# xes_cabling.net
KiCad netlist of a schematic drawn in EAGLE
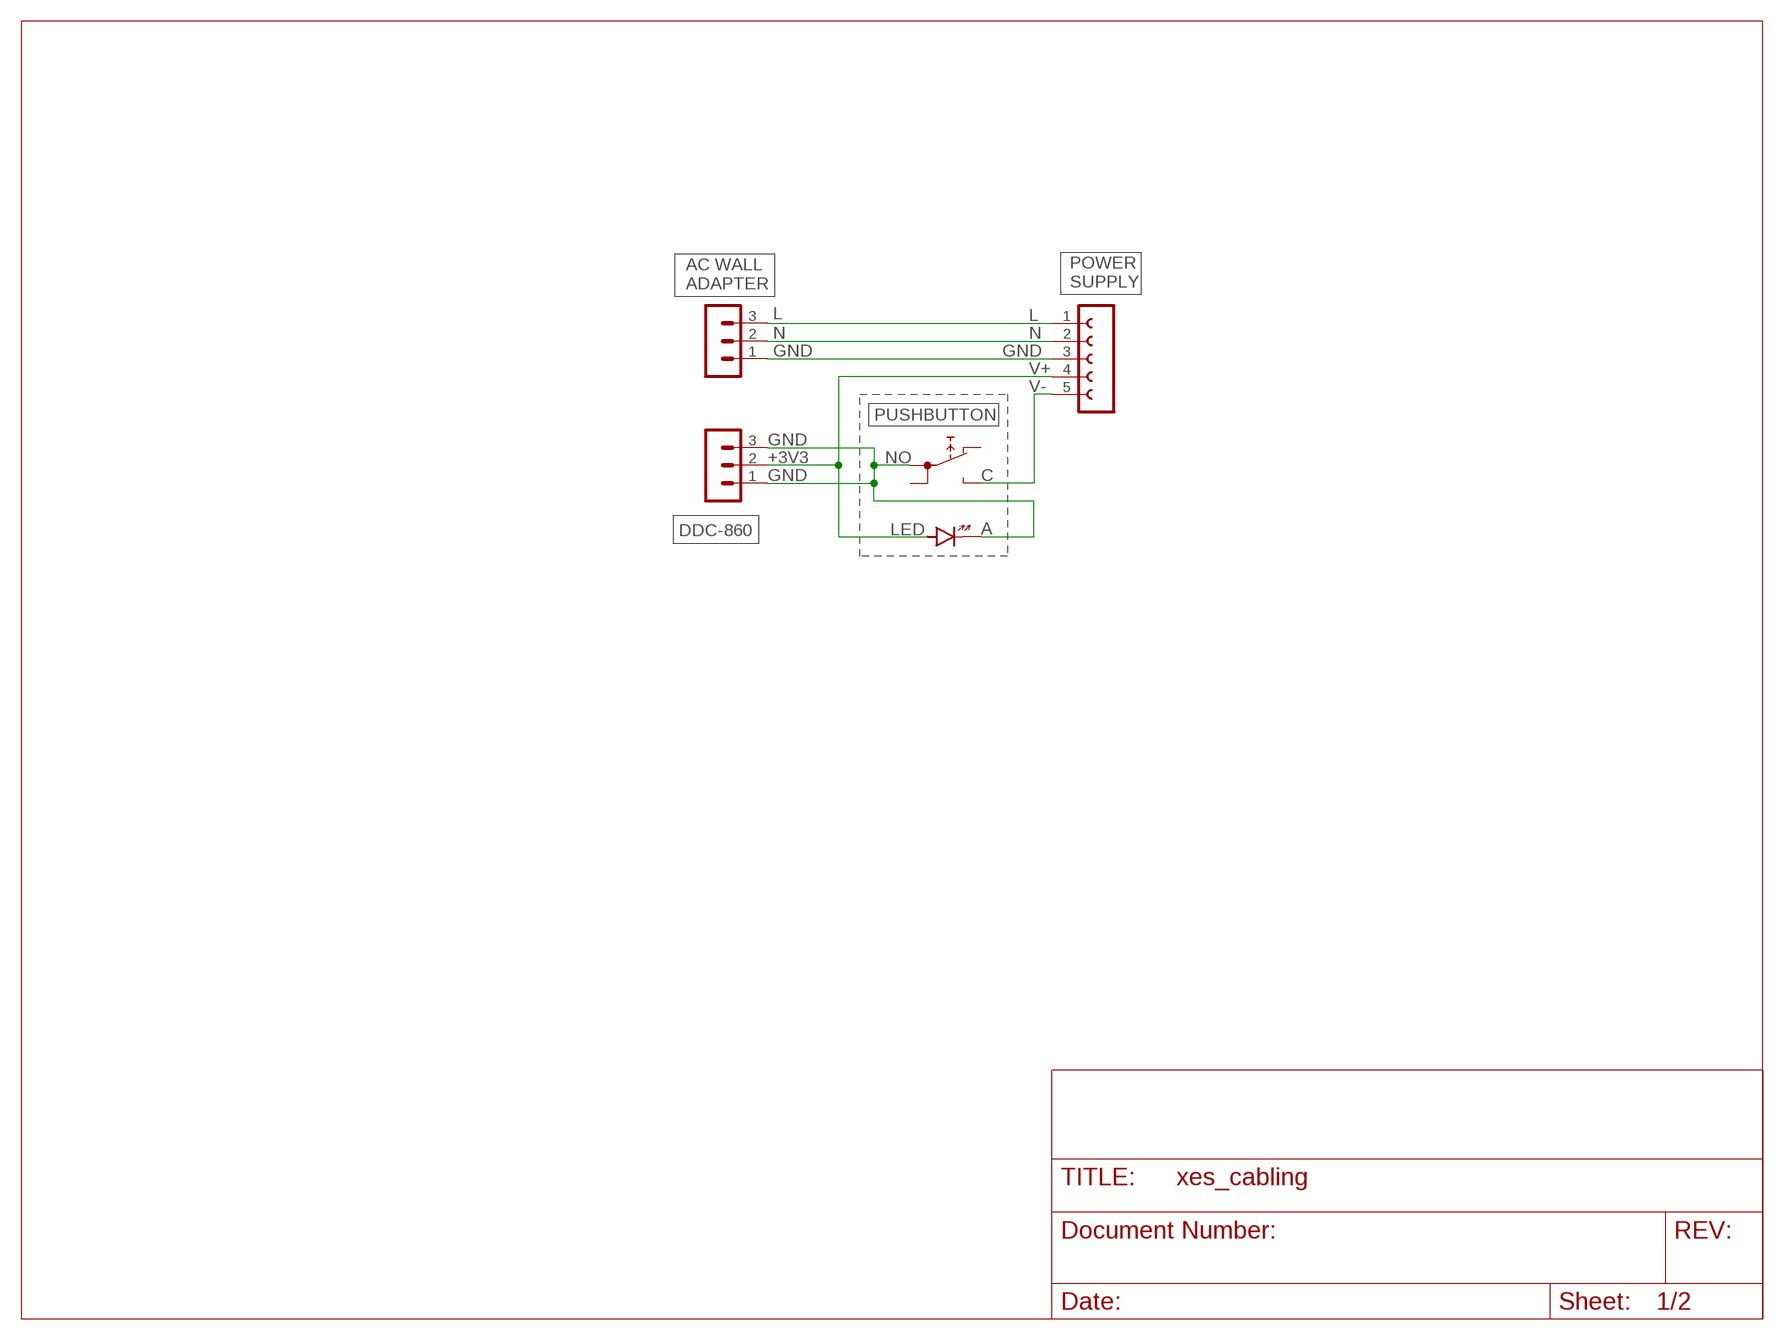
[diagram p0: schematic, sheet 1]
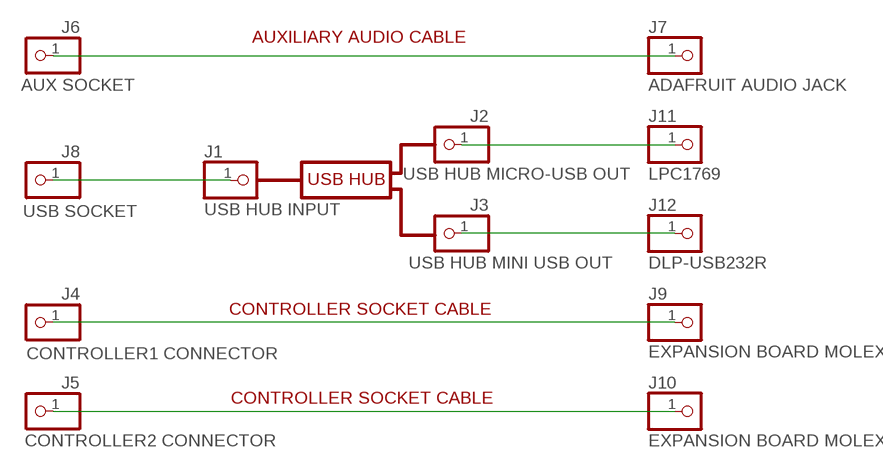
[diagram p1: schematic, sheet 2]

(export (version "E")
  (design (tool "Eeschema 10.0.6"))
  (components
    (comp (ref "LS25-3.3")
      (value "PSU")
      (footprint "eagle-import:FE05-1")
      (libsource (lib "eagle-import") (part "FE05-1"))
    )
    (comp (ref "S1")
      (value "PUSHBUTTON")
      (footprint "eagle-import:5501-1LED")
      (libsource (lib "eagle-import") (part "55?-1LED01"))
    )
    (comp (ref "SV1")
      (value "MA03-1")
      (footprint "eagle-import:MA03-1")
      (libsource (lib "eagle-import") (part "MA03-1"))
    )
    (comp (ref "SV2")
      (value "MA03-1")
      (footprint "eagle-import:MA03-1")
      (libsource (lib "eagle-import") (part "MA03-1"))
    )
    (comp (ref "J1")
      (value "USB HUB INPUT")
      (footprint "eagle-import:1X01")
      (libsource (lib "eagle-import") (part "PINHD-1X1"))
    )
    (comp (ref "J2")
      (value "USB HUB MICRO-USB OUT")
      (footprint "eagle-import:1X01")
      (libsource (lib "eagle-import") (part "PINHD-1X1"))
    )
    (comp (ref "J3")
      (value "USB HUB MINI USB OUT")
      (footprint "eagle-import:1X01")
      (libsource (lib "eagle-import") (part "PINHD-1X1"))
    )
    (comp (ref "J4")
      (value "CONTROLLER1 CONNECTOR")
      (footprint "eagle-import:1X01")
      (libsource (lib "eagle-import") (part "PINHD-1X1"))
    )
    (comp (ref "J5")
      (value "CONTROLLER2 CONNECTOR")
      (footprint "eagle-import:1X01")
      (libsource (lib "eagle-import") (part "PINHD-1X1"))
    )
    (comp (ref "J6")
      (value "AUX SOCKET")
      (footprint "eagle-import:1X01")
      (libsource (lib "eagle-import") (part "PINHD-1X1"))
    )
    (comp (ref "J7")
      (value "ADAFRUIT AUDIO JACK")
      (footprint "eagle-import:1X01")
      (libsource (lib "eagle-import") (part "PINHD-1X1"))
    )
    (comp (ref "J8")
      (value "USB SOCKET")
      (footprint "eagle-import:1X01")
      (libsource (lib "eagle-import") (part "PINHD-1X1"))
    )
    (comp (ref "J9")
      (value "EXPANSION BOARD MOLEX1")
      (footprint "eagle-import:1X01")
      (libsource (lib "eagle-import") (part "PINHD-1X1"))
    )
    (comp (ref "J10")
      (value "EXPANSION BOARD MOLEX2")
      (footprint "eagle-import:1X01")
      (libsource (lib "eagle-import") (part "PINHD-1X1"))
    )
    (comp (ref "J11")
      (value "LPC1769")
      (footprint "eagle-import:1X01")
      (libsource (lib "eagle-import") (part "PINHD-1X1"))
    )
    (comp (ref "J12")
      (value "DLP-USB232R")
      (footprint "eagle-import:1X01")
      (libsource (lib "eagle-import") (part "PINHD-1X1"))
    )
  )
  (nets
    (net (code "1") (name "C") (class "Default")
      (node (ref "LS25-3.3") (pin "5") (pinfunction "5_5") (pintype "passive"))
      (node (ref "S1") (pin "NO") (pinfunction "NO_NO") (pintype "passive"))
    )
    (net (code "2") (name "GND") (class "Default")
      (node (ref "LS25-3.3") (pin "3") (pinfunction "3_3") (pintype "passive"))
      (node (ref "S1") (pin "-") (pinfunction "K_-") (pintype "passive"))
      (node (ref "S1") (pin "1A") (pinfunction "1A_1A") (pintype "passive"))
      (node (ref "SV1") (pin "1") (pinfunction "1_1") (pintype "passive"))
      (node (ref "SV1") (pin "3") (pinfunction "3_3") (pintype "passive"))
      (node (ref "SV2") (pin "1") (pinfunction "1_1") (pintype "passive"))
    )
    (net (code "3") (name "L") (class "Default")
      (node (ref "LS25-3.3") (pin "1") (pinfunction "1_1") (pintype "passive"))
      (node (ref "SV2") (pin "3") (pinfunction "3_3") (pintype "passive"))
    )
    (net (code "4") (name "N") (class "Default")
      (node (ref "LS25-3.3") (pin "2") (pinfunction "2_2") (pintype "passive"))
      (node (ref "SV2") (pin "2") (pinfunction "2_2") (pintype "passive"))
    )
    (net (code "5") (name "Net-(J1-Pad1)") (class "Default")
      (node (ref "J1") (pin "1") (pinfunction "1_1") (pintype "passive"))
      (node (ref "J8") (pin "1") (pinfunction "1_1") (pintype "passive"))
    )
    (net (code "6") (name "Net-(J4-Pad1)") (class "Default")
      (node (ref "J4") (pin "1") (pinfunction "1_1") (pintype "passive"))
      (node (ref "J9") (pin "1") (pinfunction "1_1") (pintype "passive"))
    )
    (net (code "7") (name "Net-(J6-Pad1)") (class "Default")
      (node (ref "J6") (pin "1") (pinfunction "1_1") (pintype "passive"))
      (node (ref "J7") (pin "1") (pinfunction "1_1") (pintype "passive"))
    )
    (net (code "8") (name "Net-(J10-Pad1)") (class "Default")
      (node (ref "J10") (pin "1") (pinfunction "1_1") (pintype "passive"))
      (node (ref "J5") (pin "1") (pinfunction "1_1") (pintype "passive"))
    )
    (net (code "9") (name "Net-(J11-Pad1)") (class "Default")
      (node (ref "J11") (pin "1") (pinfunction "1_1") (pintype "passive"))
      (node (ref "J2") (pin "1") (pinfunction "1_1") (pintype "passive"))
    )
    (net (code "10") (name "Net-(J12-Pad1)") (class "Default")
      (node (ref "J12") (pin "1") (pinfunction "1_1") (pintype "passive"))
      (node (ref "J3") (pin "1") (pinfunction "1_1") (pintype "passive"))
    )
    (net (code "11") (name "V+") (class "Default")
      (node (ref "LS25-3.3") (pin "4") (pinfunction "4_4") (pintype "passive"))
      (node (ref "S1") (pin "+") (pinfunction "A_+") (pintype "passive"))
      (node (ref "SV1") (pin "2") (pinfunction "2_2") (pintype "passive"))
    )
    (net (code "12") (name "unconnected-(S1-Pad1B)") (class "Default")
      (node (ref "S1") (pin "1B") (pinfunction "1B_1B") (pintype "passive"))
    )
    (net (code "13") (name "unconnected-(S1-PadNC)") (class "Default")
      (node (ref "S1") (pin "NC") (pinfunction "NC_NC") (pintype "passive"))
    )
  )
)
